# ospi_v143.net
KiCad netlist of a schematic drawn in EAGLE
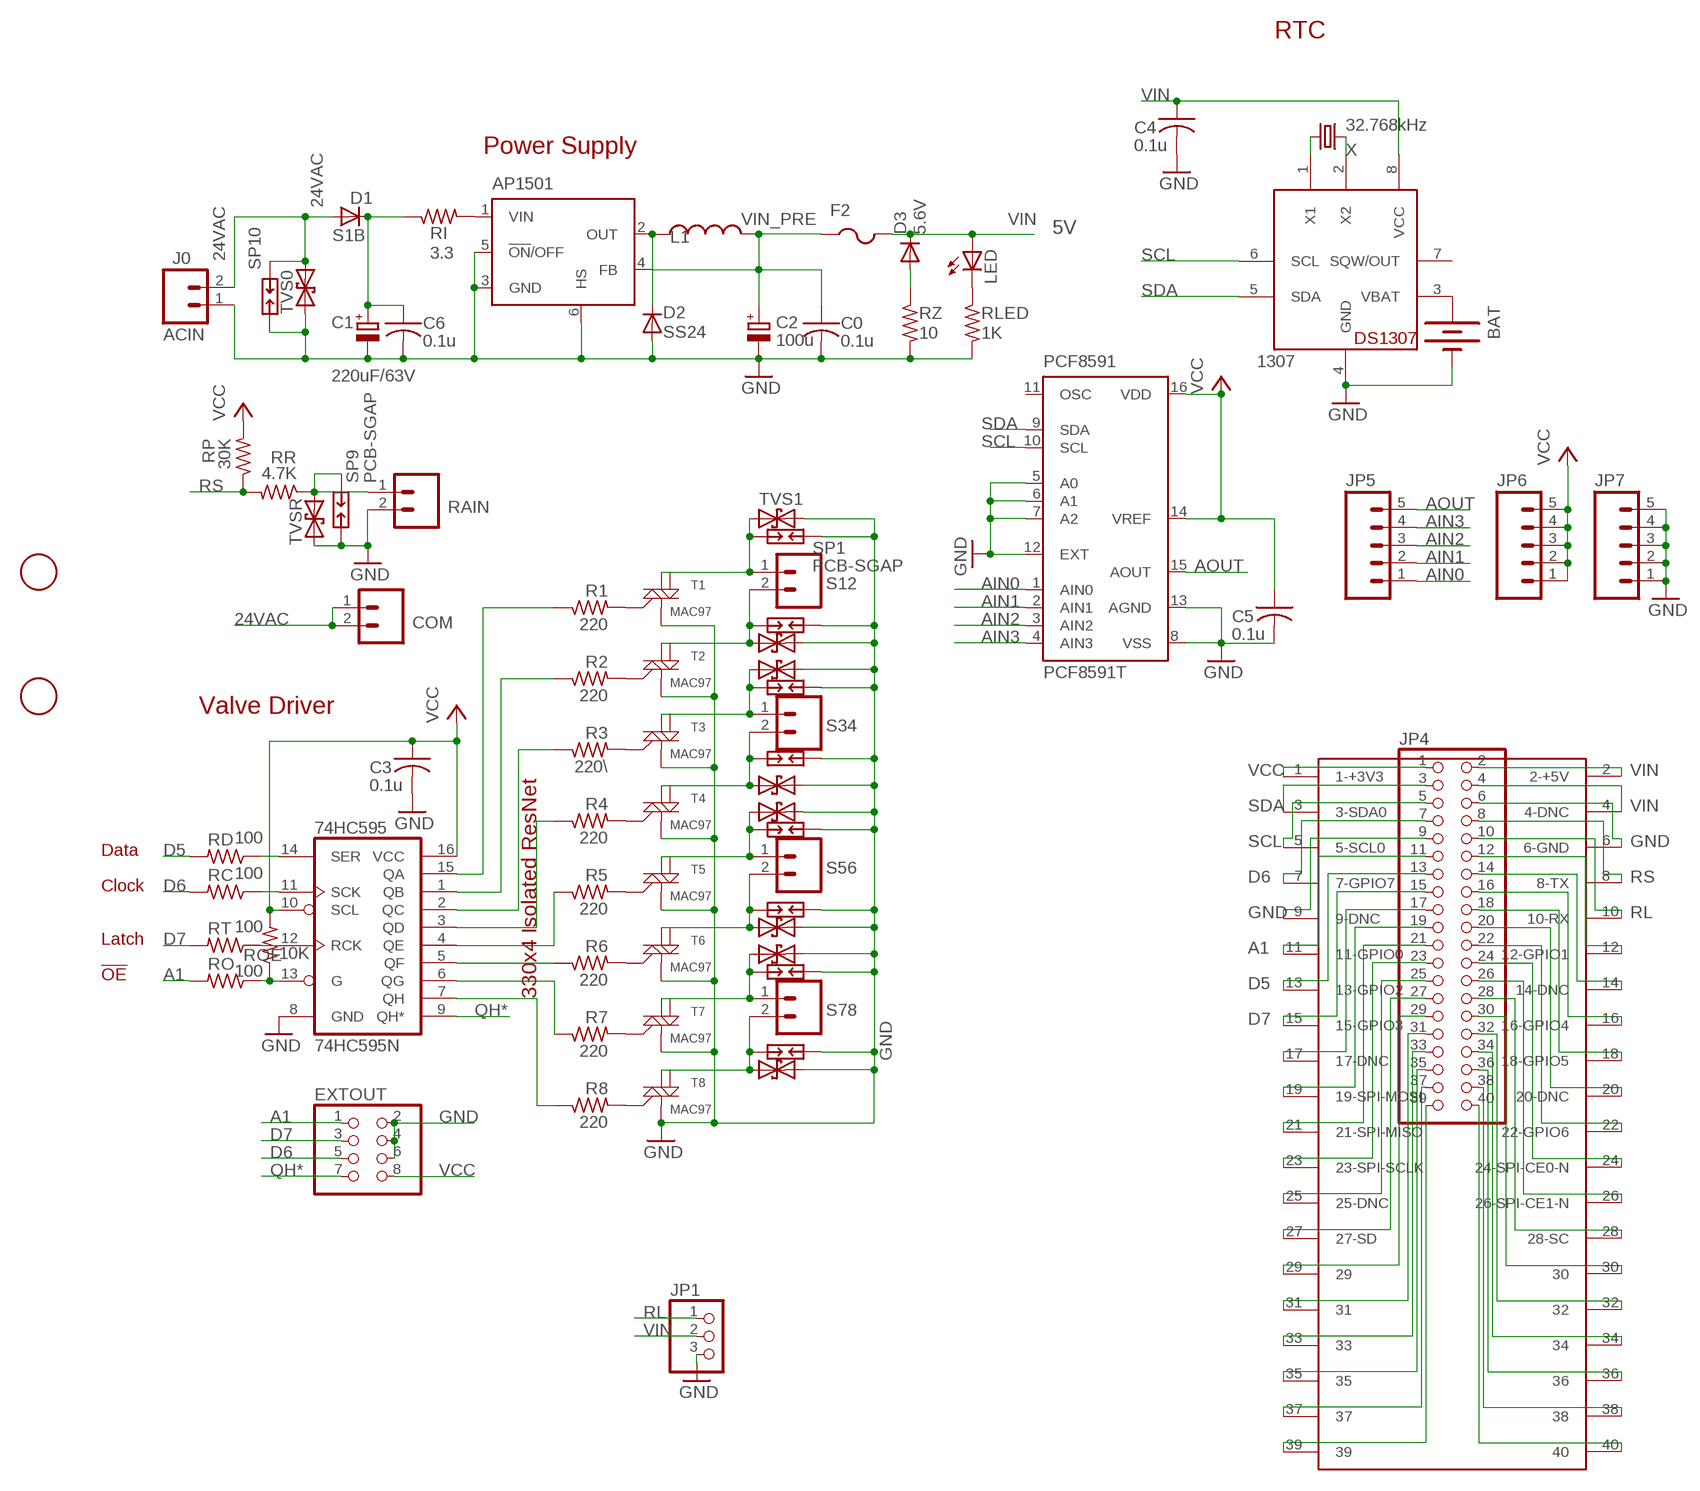
[diagram p0: schematic, sheet 1]

(export (version "E")
  (design (tool "Eeschema 10.0.6"))
  (components
    (comp (ref "74HC595")
      (value "74HC595N")
      (footprint "eagle-import:SO16")
      (libsource (lib "eagle-import") (part "74595DLS"))
    )
    (comp (ref "1307")
      (value "DS1307")
      (footprint "eagle-import:SO08")
      (libsource (lib "eagle-import") (part "DS1307SOIC"))
    )
    (comp (ref "AP1501")
      (value "LM2596S")
      (footprint "eagle-import:TO263-5")
      (fields (field (name "MF") "NATIONAL SEMICONDUCTOR") (field (name "MPN") "LM2596S-ADJ/NOPB"))
      (libsource (lib "eagle-import") (part "LM2596S"))
    )
    (comp (ref "BAT")
      (value "BATTERYBATTERY_12MM_SMT")
      (footprint "eagle-import:BATTCON_12MM_SMT")
      (libsource (lib "eagle-import") (part "BATTERYBATTERY_12MM_SMT"))
    )
    (comp (ref "C0")
      (value "0.1u")
      (footprint "eagle-import:C0603K")
      (libsource (lib "eagle-import") (part "C-USC0603K"))
    )
    (comp (ref "C1")
      (value "220uF/63V")
      (footprint "eagle-import:PANASONIC_E")
      (libsource (lib "eagle-import") (part "CPOL-EUE"))
    )
    (comp (ref "C2")
      (value "100u")
      (footprint "eagle-import:PANASONIC_E")
      (libsource (lib "eagle-import") (part "CPOL-EUE"))
    )
    (comp (ref "C3")
      (value "0.1u")
      (footprint "eagle-import:C0603K")
      (libsource (lib "eagle-import") (part "C-USC0603K"))
    )
    (comp (ref "C4")
      (value "0.1u")
      (footprint "eagle-import:C0603K")
      (libsource (lib "eagle-import") (part "C-USC0603K"))
    )
    (comp (ref "C5")
      (value "0.1u")
      (footprint "eagle-import:C0603K")
      (libsource (lib "eagle-import") (part "C-USC0603K"))
    )
    (comp (ref "C6")
      (value "0.1u")
      (footprint "eagle-import:C0603K")
      (libsource (lib "eagle-import") (part "C-USC0603K"))
    )
    (comp (ref "COM")
      (value "M025MM-X")
      (footprint "eagle-import:SCREWTERMINAL-5MM-2-X")
      (libsource (lib "eagle-import") (part "M025MM-X"))
    )
    (comp (ref "D1")
      (value "S1B")
      (footprint "eagle-import:DO-214AC")
      (libsource (lib "eagle-import") (part "DIODE-DO-214AC"))
    )
    (comp (ref "D2")
      (value "SS24")
      (footprint "eagle-import:SMB")
      (libsource (lib "eagle-import") (part "DIODE-SMB"))
    )
    (comp (ref "D3")
      (value "5.6V")
      (footprint "eagle-import:MINIMELF")
      (libsource (lib "eagle-import") (part "DIODE-MINIMELF"))
    )
    (comp (ref "EXTOUT")
      (value "PINHD-2X4/90")
      (footprint "eagle-import:2X04_90")
      (libsource (lib "eagle-import") (part "PINHD-2X4/90"))
    )
    (comp (ref "F2")
      (value "PTCFUSE-1812")
      (footprint "eagle-import:1812")
      (libsource (lib "eagle-import") (part "PTCFUSE-1812"))
    )
    (comp (ref "J0")
      (value "ACIN")
      (footprint "eagle-import:SCREWTERMINAL-4MM-2-X")
      (libsource (lib "eagle-import") (part "M024MM-X"))
    )
    (comp (ref "JP1")
      (value "PINHD-1X3")
      (footprint "eagle-import:1X03")
      (libsource (lib "eagle-import") (part "PINHD-1X3"))
    )
    (comp (ref "JP4")
      (value "PINHD-2X20")
      (footprint "eagle-import:2X20")
      (libsource (lib "eagle-import") (part "PINHD-2X20"))
    )
    (comp (ref "JP5")
      (value "M05PTH")
      (footprint "eagle-import:1X05")
      (libsource (lib "eagle-import") (part "M05PTH"))
    )
    (comp (ref "JP6")
      (value "M05PTH")
      (footprint "eagle-import:1X05")
      (libsource (lib "eagle-import") (part "M05PTH"))
    )
    (comp (ref "JP7")
      (value "M05PTH")
      (footprint "eagle-import:1X05")
      (libsource (lib "eagle-import") (part "M05PTH"))
    )
    (comp (ref "L1")
      (value "150uH")
      (footprint "eagle-import:CDRH125")
      (libsource (lib "eagle-import") (part "INDUCTORPWR"))
    )
    (comp (ref "LED")
      (value "LEDCHIPLED_0805")
      (footprint "eagle-import:CHIPLED_0805")
      (libsource (lib "eagle-import") (part "LEDCHIPLED_0805"))
    )
    (comp (ref "PCF8591")
      (value "PCF8591T")
      (footprint "eagle-import:SO16W")
      (fields (field (name "MPN") "PCF8591T/2,512"))
      (libsource (lib "eagle-import") (part "PCF8591T"))
    )
    (comp (ref "R1")
      (value "220")
      (footprint "eagle-import:R0603")
      (libsource (lib "eagle-import") (part "R-US_R0603"))
    )
    (comp (ref "R2")
      (value "220")
      (footprint "eagle-import:R0603")
      (libsource (lib "eagle-import") (part "R-US_R0603"))
    )
    (comp (ref "R3")
      (value "220\\")
      (footprint "eagle-import:R0603")
      (libsource (lib "eagle-import") (part "R-US_R0603"))
    )
    (comp (ref "R4")
      (value "220")
      (footprint "eagle-import:R0603")
      (libsource (lib "eagle-import") (part "R-US_R0603"))
    )
    (comp (ref "R5")
      (value "220")
      (footprint "eagle-import:R0603")
      (libsource (lib "eagle-import") (part "R-US_R0603"))
    )
    (comp (ref "R6")
      (value "220")
      (footprint "eagle-import:R0603")
      (libsource (lib "eagle-import") (part "R-US_R0603"))
    )
    (comp (ref "R7")
      (value "220")
      (footprint "eagle-import:R0603")
      (libsource (lib "eagle-import") (part "R-US_R0603"))
    )
    (comp (ref "R8")
      (value "220")
      (footprint "eagle-import:R0603")
      (libsource (lib "eagle-import") (part "R-US_R0603"))
    )
    (comp (ref "RAIN")
      (value "M025MM-X")
      (footprint "eagle-import:SCREWTERMINAL-5MM-2-X")
      (libsource (lib "eagle-import") (part "M025MM-X"))
    )
    (comp (ref "RC")
      (value "100")
      (footprint "eagle-import:R0603")
      (libsource (lib "eagle-import") (part "R-US_R0603"))
    )
    (comp (ref "RD")
      (value "100")
      (footprint "eagle-import:R0603")
      (libsource (lib "eagle-import") (part "R-US_R0603"))
    )
    (comp (ref "RI")
      (value "3.3")
      (footprint "eagle-import:R2010")
      (libsource (lib "eagle-import") (part "adafruitGood_R-US_R2010"))
    )
    (comp (ref "RLED")
      (value "1K")
      (footprint "eagle-import:R0805")
      (libsource (lib "eagle-import") (part "R-US_R0805"))
    )
    (comp (ref "RO")
      (value "100")
      (footprint "eagle-import:R0603")
      (libsource (lib "eagle-import") (part "R-US_R0603"))
    )
    (comp (ref "ROE")
      (value "10K")
      (footprint "eagle-import:R0603")
      (libsource (lib "eagle-import") (part "R-US_R0603"))
    )
    (comp (ref "RP")
      (value "30K")
      (footprint "eagle-import:R0805")
      (libsource (lib "eagle-import") (part "R-US_R0805"))
    )
    (comp (ref "RR")
      (value "4.7K")
      (footprint "eagle-import:R0805")
      (libsource (lib "eagle-import") (part "R-US_R0805"))
    )
    (comp (ref "RT")
      (value "100")
      (footprint "eagle-import:R0603")
      (libsource (lib "eagle-import") (part "R-US_R0603"))
    )
    (comp (ref "RZ")
      (value "10")
      (footprint "eagle-import:R2010")
      (libsource (lib "eagle-import") (part "R-US_R2010"))
    )
    (comp (ref "S12")
      (value "M025MM-X")
      (footprint "eagle-import:SCREWTERMINAL-5MM-2-X")
      (libsource (lib "eagle-import") (part "M025MM-X"))
    )
    (comp (ref "S34")
      (value "M025MM-X")
      (footprint "eagle-import:SCREWTERMINAL-5MM-2-X")
      (libsource (lib "eagle-import") (part "M025MM-X"))
    )
    (comp (ref "S56")
      (value "M025MM-X")
      (footprint "eagle-import:SCREWTERMINAL-5MM-2-X")
      (libsource (lib "eagle-import") (part "M025MM-X"))
    )
    (comp (ref "S78")
      (value "M025MM-X")
      (footprint "eagle-import:SCREWTERMINAL-5MM-2-X")
      (libsource (lib "eagle-import") (part "M025MM-X"))
    )
    (comp (ref "SP1")
      (value "PCB-SGAP")
      (footprint "eagle-import:PCB-SGAP")
      (libsource (lib "eagle-import") (part "PCB-SGAP"))
    )
    (comp (ref "SP2")
      (value "PCB-SGAP")
      (footprint "eagle-import:PCB-SGAP")
      (libsource (lib "eagle-import") (part "PCB-SGAP"))
    )
    (comp (ref "SP3")
      (value "PCB-SGAP")
      (footprint "eagle-import:PCB-SGAP")
      (libsource (lib "eagle-import") (part "PCB-SGAP"))
    )
    (comp (ref "SP4")
      (value "PCB-SGAP")
      (footprint "eagle-import:PCB-SGAP")
      (libsource (lib "eagle-import") (part "PCB-SGAP"))
    )
    (comp (ref "SP5")
      (value "PCB-SGAP")
      (footprint "eagle-import:PCB-SGAP")
      (libsource (lib "eagle-import") (part "PCB-SGAP"))
    )
    (comp (ref "SP6")
      (value "PCB-SGAP")
      (footprint "eagle-import:PCB-SGAP")
      (libsource (lib "eagle-import") (part "PCB-SGAP"))
    )
    (comp (ref "SP7")
      (value "PCB-SGAP")
      (footprint "eagle-import:PCB-SGAP")
      (libsource (lib "eagle-import") (part "PCB-SGAP"))
    )
    (comp (ref "SP8")
      (value "PCB-SGAP")
      (footprint "eagle-import:PCB-SGAP")
      (libsource (lib "eagle-import") (part "PCB-SGAP"))
    )
    (comp (ref "SP9")
      (value "PCB-SGAP")
      (footprint "eagle-import:PCB-SGAP")
      (libsource (lib "eagle-import") (part "PCB-SGAP"))
    )
    (comp (ref "SP10")
      (value "PCB-SGAP")
      (footprint "eagle-import:PCB-SGAP")
      (libsource (lib "eagle-import") (part "PCB-SGAP"))
    )
    (comp (ref "T1")
      (value "MAC97")
      (footprint "eagle-import:SOT223")
      (libsource (lib "eagle-import") (part "MAC97SOT223"))
    )
    (comp (ref "T2")
      (value "MAC97")
      (footprint "eagle-import:SOT223")
      (libsource (lib "eagle-import") (part "MAC97SOT223"))
    )
    (comp (ref "T3")
      (value "MAC97")
      (footprint "eagle-import:SOT223")
      (libsource (lib "eagle-import") (part "MAC97SOT223"))
    )
    (comp (ref "T4")
      (value "MAC97")
      (footprint "eagle-import:SOT223")
      (libsource (lib "eagle-import") (part "MAC97SOT223"))
    )
    (comp (ref "T5")
      (value "MAC97")
      (footprint "eagle-import:SOT223")
      (libsource (lib "eagle-import") (part "MAC97SOT223"))
    )
    (comp (ref "T6")
      (value "MAC97")
      (footprint "eagle-import:SOT223")
      (libsource (lib "eagle-import") (part "MAC97SOT223"))
    )
    (comp (ref "T7")
      (value "MAC97")
      (footprint "eagle-import:SOT223")
      (libsource (lib "eagle-import") (part "MAC97SOT223"))
    )
    (comp (ref "T8")
      (value "MAC97")
      (footprint "eagle-import:SOT223")
      (libsource (lib "eagle-import") (part "MAC97SOT223"))
    )
    (comp (ref "TVS0")
      (value "TVSSMB")
      (footprint "eagle-import:SMB")
      (libsource (lib "eagle-import") (part "TVSSMB"))
    )
    (comp (ref "TVS1")
      (value "TVSSMB")
      (footprint "eagle-import:SMB")
      (libsource (lib "eagle-import") (part "TVSSMB"))
    )
    (comp (ref "TVS2")
      (value "TVSSMB")
      (footprint "eagle-import:SMB")
      (libsource (lib "eagle-import") (part "TVSSMB"))
    )
    (comp (ref "TVS3")
      (value "TVSSMB")
      (footprint "eagle-import:SMB")
      (libsource (lib "eagle-import") (part "TVSSMB"))
    )
    (comp (ref "TVS4")
      (value "TVSSMB")
      (footprint "eagle-import:SMB")
      (libsource (lib "eagle-import") (part "TVSSMB"))
    )
    (comp (ref "TVS5")
      (value "TVSSMB")
      (footprint "eagle-import:SMB")
      (libsource (lib "eagle-import") (part "TVSSMB"))
    )
    (comp (ref "TVS6")
      (value "TVSSMB")
      (footprint "eagle-import:SMB")
      (libsource (lib "eagle-import") (part "TVSSMB"))
    )
    (comp (ref "TVS7")
      (value "TVSSMB")
      (footprint "eagle-import:SMB")
      (libsource (lib "eagle-import") (part "TVSSMB"))
    )
    (comp (ref "TVS8")
      (value "TVSSMB")
      (footprint "eagle-import:SMB")
      (libsource (lib "eagle-import") (part "TVSSMB"))
    )
    (comp (ref "TVSR")
      (value "TVSSMB")
      (footprint "eagle-import:SMB")
      (libsource (lib "eagle-import") (part "TVSSMB"))
    )
    (comp (ref "U$1")
      (value "FIDUCIAL")
      (footprint "eagle-import:FIDUCIAL_1MM")
      (libsource (lib "eagle-import") (part "FIDUCIAL"))
    )
    (comp (ref "U$2")
      (value "RPIB+")
      (footprint "eagle-import:RPIB+")
      (libsource (lib "eagle-import") (part "RPIB+"))
    )
    (comp (ref "U$3")
      (value "FIDUCIAL")
      (footprint "eagle-import:FIDUCIAL_1MM")
      (libsource (lib "eagle-import") (part "FIDUCIAL"))
    )
    (comp (ref "X")
      (value "32.768kHz")
      (footprint "eagle-import:MM20SS")
      (libsource (lib "eagle-import") (part "CRYSTALMM20SS"))
    )
  )
  (nets
    (net (code "1") (name "/24VAC") (class "Default")
      (node (ref "COM") (pin "1") (pinfunction "1_1") (pintype "passive"))
      (node (ref "COM") (pin "2") (pinfunction "2_2") (pintype "passive"))
      (node (ref "D1") (pin "A") (pinfunction "A_A") (pintype "passive"))
      (node (ref "J0") (pin "2") (pinfunction "2_2") (pintype "passive"))
      (node (ref "SP10") (pin "1") (pinfunction "1_1") (pintype "passive"))
      (node (ref "TVS0") (pin "C") (pinfunction "C_C") (pintype "passive"))
    )
    (net (code "2") (name "/A1") (class "Default")
      (node (ref "EXTOUT") (pin "1") (pinfunction "1_1") (pintype "passive"))
      (node (ref "JP4") (pin "11") (pinfunction "11_11") (pintype "passive"))
      (node (ref "RO") (pin "2") (pinfunction "2_2") (pintype "passive"))
      (node (ref "U$2") (pin "11") (pinfunction "11-GPIO0_11") (pintype "bidirectional"))
    )
    (net (code "3") (name "/AIN0") (class "Default")
      (node (ref "JP5") (pin "1") (pinfunction "1_1") (pintype "passive"))
      (node (ref "PCF8591") (pin "1") (pinfunction "AIN0_1") (pintype "input"))
    )
    (net (code "4") (name "/AIN1") (class "Default")
      (node (ref "JP5") (pin "2") (pinfunction "2_2") (pintype "passive"))
      (node (ref "PCF8591") (pin "2") (pinfunction "AIN1_2") (pintype "input"))
    )
    (net (code "5") (name "/AIN2") (class "Default")
      (node (ref "JP5") (pin "3") (pinfunction "3_3") (pintype "passive"))
      (node (ref "PCF8591") (pin "3") (pinfunction "AIN2_3") (pintype "input"))
    )
    (net (code "6") (name "/AIN3") (class "Default")
      (node (ref "JP5") (pin "4") (pinfunction "4_4") (pintype "passive"))
      (node (ref "PCF8591") (pin "4") (pinfunction "AIN3_4") (pintype "input"))
    )
    (net (code "7") (name "/AOUT") (class "Default")
      (node (ref "JP5") (pin "5") (pinfunction "5_5") (pintype "passive"))
      (node (ref "PCF8591") (pin "15") (pinfunction "AOUT_15") (pintype "output"))
    )
    (net (code "8") (name "/D5") (class "Default")
      (node (ref "JP4") (pin "13") (pinfunction "13_13") (pintype "passive"))
      (node (ref "RD") (pin "2") (pinfunction "2_2") (pintype "passive"))
      (node (ref "U$2") (pin "13") (pinfunction "13-GPIO2_13") (pintype "bidirectional"))
    )
    (net (code "9") (name "/D6") (class "Default")
      (node (ref "EXTOUT") (pin "5") (pinfunction "5_5") (pintype "passive"))
      (node (ref "JP4") (pin "7") (pinfunction "7_7") (pintype "passive"))
      (node (ref "RC") (pin "2") (pinfunction "2_2") (pintype "passive"))
      (node (ref "U$2") (pin "7") (pinfunction "7-GPIO7_7") (pintype "bidirectional"))
    )
    (net (code "10") (name "/D7") (class "Default")
      (node (ref "EXTOUT") (pin "3") (pinfunction "3_3") (pintype "passive"))
      (node (ref "JP4") (pin "15") (pinfunction "15_15") (pintype "passive"))
      (node (ref "RT") (pin "2") (pinfunction "2_2") (pintype "passive"))
      (node (ref "U$2") (pin "15") (pinfunction "15-GPIO3_15") (pintype "bidirectional"))
    )
    (net (code "11") (name "/QH*") (class "Default")
      (node (ref "74HC595") (pin "9") (pinfunction "QH*_9") (pintype "tri_state"))
      (node (ref "EXTOUT") (pin "7") (pinfunction "7_7") (pintype "passive"))
    )
    (net (code "12") (name "/RL") (class "Default")
      (node (ref "JP1") (pin "1") (pinfunction "1_1") (pintype "passive"))
      (node (ref "JP4") (pin "10") (pinfunction "10_10") (pintype "passive"))
      (node (ref "U$2") (pin "10") (pinfunction "10-RX_10") (pintype "bidirectional"))
    )
    (net (code "13") (name "/RS") (class "Default")
      (node (ref "JP4") (pin "8") (pinfunction "8_8") (pintype "passive"))
      (node (ref "RP") (pin "1") (pinfunction "1_1") (pintype "passive"))
      (node (ref "RR") (pin "2") (pinfunction "2_2") (pintype "passive"))
      (node (ref "U$2") (pin "8") (pinfunction "8-TX_8") (pintype "bidirectional"))
    )
    (net (code "14") (name "/SCL") (class "Default")
      (node (ref "1307") (pin "6") (pinfunction "SCL_6") (pintype "bidirectional"))
      (node (ref "JP4") (pin "5") (pinfunction "5_5") (pintype "passive"))
      (node (ref "PCF8591") (pin "10") (pinfunction "SCL_10") (pintype "input"))
      (node (ref "U$2") (pin "5") (pinfunction "5-SCL0_5") (pintype "bidirectional"))
    )
    (net (code "15") (name "/SDA") (class "Default")
      (node (ref "1307") (pin "5") (pinfunction "SDA_5") (pintype "bidirectional"))
      (node (ref "JP4") (pin "3") (pinfunction "3_3") (pintype "passive"))
      (node (ref "PCF8591") (pin "9") (pinfunction "SDA_9") (pintype "bidirectional"))
      (node (ref "U$2") (pin "3") (pinfunction "3-SDA0_3") (pintype "bidirectional"))
    )
    (net (code "16") (name "/VIN") (class "Default")
      (node (ref "1307") (pin "8") (pinfunction "VCC_8") (pintype "power_in"))
      (node (ref "C4") (pin "1") (pinfunction "1_1") (pintype "passive"))
      (node (ref "D3") (pin "C") (pinfunction "C_C") (pintype "passive"))
      (node (ref "F2") (pin "2") (pinfunction "2_2") (pintype "passive"))
      (node (ref "JP1") (pin "2") (pinfunction "2_2") (pintype "passive"))
      (node (ref "JP4") (pin "2") (pinfunction "2_2") (pintype "passive"))
      (node (ref "JP4") (pin "4") (pinfunction "4_4") (pintype "passive"))
      (node (ref "LED") (pin "A") (pinfunction "A_A") (pintype "passive"))
      (node (ref "U$2") (pin "2") (pinfunction "2-+5V_2") (pintype "bidirectional"))
      (node (ref "U$2") (pin "4") (pinfunction "4-DNC_4") (pintype "bidirectional"))
    )
    (net (code "17") (name "/VIN_PRE") (class "Default")
      (node (ref "AP1501") (pin "4") (pinfunction "FB_4") (pintype "input"))
      (node (ref "C0") (pin "1") (pinfunction "1_1") (pintype "passive"))
      (node (ref "C2") (pin "+") (pinfunction "+_+") (pintype "passive"))
      (node (ref "F2") (pin "1") (pinfunction "1_1") (pintype "passive"))
      (node (ref "L1") (pin "2") (pinfunction "2_2") (pintype "passive"))
    )
    (net (code "18") (name "GND") (class "Default")
      (node (ref "1307") (pin "4") (pinfunction "GND_4") (pintype "power_in"))
      (node (ref "74HC595") (pin "8") (pinfunction "GND_8") (pintype "power_in"))
      (node (ref "AP1501") (pin "3") (pinfunction "GND_3") (pintype "power_in"))
      (node (ref "AP1501") (pin "5") (pinfunction "~{ON}/OFF_5") (pintype "input"))
      (node (ref "AP1501") (pin "6") (pinfunction "HS_6") (pintype "power_in"))
      (node (ref "BAT") (pin "P$1") (pinfunction "-_P$1") (pintype "power_in"))
      (node (ref "C0") (pin "2") (pinfunction "2_2") (pintype "passive"))
      (node (ref "C1") (pin "-") (pinfunction "-_-") (pintype "passive"))
      (node (ref "C2") (pin "-") (pinfunction "-_-") (pintype "passive"))
      (node (ref "C3") (pin "2") (pinfunction "2_2") (pintype "passive"))
      (node (ref "C4") (pin "2") (pinfunction "2_2") (pintype "passive"))
      (node (ref "C5") (pin "2") (pinfunction "2_2") (pintype "passive"))
      (node (ref "C6") (pin "2") (pinfunction "2_2") (pintype "passive"))
      (node (ref "D2") (pin "A") (pinfunction "A_A") (pintype "passive"))
      (node (ref "EXTOUT") (pin "2") (pinfunction "2_2") (pintype "passive"))
      (node (ref "EXTOUT") (pin "4") (pinfunction "4_4") (pintype "passive"))
      (node (ref "EXTOUT") (pin "6") (pinfunction "6_6") (pintype "passive"))
      (node (ref "J0") (pin "1") (pinfunction "1_1") (pintype "passive"))
      (node (ref "JP1") (pin "3") (pinfunction "3_3") (pintype "passive"))
      (node (ref "JP4") (pin "6") (pinfunction "6_6") (pintype "passive"))
      (node (ref "JP4") (pin "9") (pinfunction "9_9") (pintype "passive"))
      (node (ref "JP7") (pin "1") (pinfunction "1_1") (pintype "passive"))
      (node (ref "JP7") (pin "2") (pinfunction "2_2") (pintype "passive"))
      (node (ref "JP7") (pin "3") (pinfunction "3_3") (pintype "passive"))
      (node (ref "JP7") (pin "4") (pinfunction "4_4") (pintype "passive"))
      (node (ref "JP7") (pin "5") (pinfunction "5_5") (pintype "passive"))
      (node (ref "PCF8591") (pin "12") (pinfunction "EXT_12") (pintype "input"))
      (node (ref "PCF8591") (pin "13") (pinfunction "AGND_13") (pintype "power_in"))
      (node (ref "PCF8591") (pin "5") (pinfunction "A0_5") (pintype "input"))
      (node (ref "PCF8591") (pin "6") (pinfunction "A1_6") (pintype "input"))
      (node (ref "PCF8591") (pin "7") (pinfunction "A2_7") (pintype "input"))
      (node (ref "PCF8591") (pin "8") (pinfunction "VSS_8") (pintype "power_in"))
      (node (ref "RAIN") (pin "2") (pinfunction "2_2") (pintype "passive"))
      (node (ref "RLED") (pin "2") (pinfunction "2_2") (pintype "passive"))
      (node (ref "RZ") (pin "2") (pinfunction "2_2") (pintype "passive"))
      (node (ref "SP1") (pin "1") (pinfunction "1_1") (pintype "passive"))
      (node (ref "SP10") (pin "2") (pinfunction "2_2") (pintype "passive"))
      (node (ref "SP2") (pin "1") (pinfunction "1_1") (pintype "passive"))
      (node (ref "SP3") (pin "1") (pinfunction "1_1") (pintype "passive"))
      (node (ref "SP4") (pin "1") (pinfunction "1_1") (pintype "passive"))
      (node (ref "SP5") (pin "1") (pinfunction "1_1") (pintype "passive"))
      (node (ref "SP6") (pin "1") (pinfunction "1_1") (pintype "passive"))
      (node (ref "SP7") (pin "1") (pinfunction "1_1") (pintype "passive"))
      (node (ref "SP8") (pin "1") (pinfunction "1_1") (pintype "passive"))
      (node (ref "SP9") (pin "2") (pinfunction "2_2") (pintype "passive"))
      (node (ref "T1") (pin "1") (pinfunction "M1_1") (pintype "bidirectional"))
      (node (ref "T2") (pin "1") (pinfunction "M1_1") (pintype "bidirectional"))
      (node (ref "T3") (pin "1") (pinfunction "M1_1") (pintype "bidirectional"))
      (node (ref "T4") (pin "1") (pinfunction "M1_1") (pintype "bidirectional"))
      (node (ref "T5") (pin "1") (pinfunction "M1_1") (pintype "bidirectional"))
      (node (ref "T6") (pin "1") (pinfunction "M1_1") (pintype "bidirectional"))
      (node (ref "T7") (pin "1") (pinfunction "M1_1") (pintype "bidirectional"))
      (node (ref "T8") (pin "1") (pinfunction "M1_1") (pintype "bidirectional"))
      (node (ref "TVS0") (pin "A") (pinfunction "A_A") (pintype "passive"))
      (node (ref "TVS1") (pin "C") (pinfunction "C_C") (pintype "passive"))
      (node (ref "TVS2") (pin "C") (pinfunction "C_C") (pintype "passive"))
      (node (ref "TVS3") (pin "C") (pinfunction "C_C") (pintype "passive"))
      (node (ref "TVS4") (pin "C") (pinfunction "C_C") (pintype "passive"))
      (node (ref "TVS5") (pin "C") (pinfunction "C_C") (pintype "passive"))
      (node (ref "TVS6") (pin "C") (pinfunction "C_C") (pintype "passive"))
      (node (ref "TVS7") (pin "C") (pinfunction "C_C") (pintype "passive"))
      (node (ref "TVS8") (pin "C") (pinfunction "C_C") (pintype "passive"))
      (node (ref "TVSR") (pin "A") (pinfunction "A_A") (pintype "passive"))
      (node (ref "U$2") (pin "6") (pinfunction "6-GND_6") (pintype "bidirectional"))
      (node (ref "U$2") (pin "9") (pinfunction "9-DNC_9") (pintype "bidirectional"))
    )
    (net (code "19") (name "Net-(74HC595-G)") (class "Default")
      (node (ref "74HC595") (pin "13") (pinfunction "G_13") (pintype "input"))
      (node (ref "RO") (pin "1") (pinfunction "1_1") (pintype "passive"))
      (node (ref "ROE") (pin "1") (pinfunction "1_1") (pintype "passive"))
    )
    (net (code "20") (name "Net-(74HC595-QA)") (class "Default")
      (node (ref "74HC595") (pin "15") (pinfunction "QA_15") (pintype "tri_state"))
      (node (ref "R1") (pin "1") (pinfunction "1_1") (pintype "passive"))
    )
    (net (code "21") (name "Net-(74HC595-QB)") (class "Default")
      (node (ref "74HC595") (pin "1") (pinfunction "QB_1") (pintype "tri_state"))
      (node (ref "R2") (pin "1") (pinfunction "1_1") (pintype "passive"))
    )
    (net (code "22") (name "Net-(74HC595-QC)") (class "Default")
      (node (ref "74HC595") (pin "2") (pinfunction "QC_2") (pintype "tri_state"))
      (node (ref "R3") (pin "1") (pinfunction "1_1") (pintype "passive"))
    )
    (net (code "23") (name "Net-(74HC595-QD)") (class "Default")
      (node (ref "74HC595") (pin "3") (pinfunction "QD_3") (pintype "tri_state"))
      (node (ref "R4") (pin "1") (pinfunction "1_1") (pintype "passive"))
    )
    (net (code "24") (name "Net-(74HC595-QE)") (class "Default")
      (node (ref "74HC595") (pin "4") (pinfunction "QE_4") (pintype "tri_state"))
      (node (ref "R5") (pin "1") (pinfunction "1_1") (pintype "passive"))
    )
    (net (code "25") (name "Net-(74HC595-QF)") (class "Default")
      (node (ref "74HC595") (pin "5") (pinfunction "QF_5") (pintype "tri_state"))
      (node (ref "R6") (pin "1") (pinfunction "1_1") (pintype "passive"))
    )
    (net (code "26") (name "Net-(74HC595-QG)") (class "Default")
      (node (ref "74HC595") (pin "6") (pinfunction "QG_6") (pintype "tri_state"))
      (node (ref "R7") (pin "1") (pinfunction "1_1") (pintype "passive"))
    )
    (net (code "27") (name "Net-(74HC595-QH)") (class "Default")
      (node (ref "74HC595") (pin "7") (pinfunction "QH_7") (pintype "tri_state"))
      (node (ref "R8") (pin "1") (pinfunction "1_1") (pintype "passive"))
    )
    (net (code "28") (name "Net-(74HC595-RCK)") (class "Default")
      (node (ref "74HC595") (pin "12") (pinfunction "RCK_12") (pintype "input"))
      (node (ref "RT") (pin "1") (pinfunction "1_1") (pintype "passive"))
    )
    (net (code "29") (name "Net-(74HC595-SCK)") (class "Default")
      (node (ref "74HC595") (pin "11") (pinfunction "SCK_11") (pintype "input"))
      (node (ref "RC") (pin "1") (pinfunction "1_1") (pintype "passive"))
    )
    (net (code "30") (name "Net-(74HC595-SER)") (class "Default")
      (node (ref "74HC595") (pin "14") (pinfunction "SER_14") (pintype "input"))
      (node (ref "RD") (pin "1") (pinfunction "1_1") (pintype "passive"))
    )
    (net (code "31") (name "Net-(1307-VBAT)") (class "Default")
      (node (ref "1307") (pin "3") (pinfunction "VBAT_3") (pintype "power_in"))
      (node (ref "BAT") (pin "P$2") (pinfunction "+_P$2") (pintype "power_in"))
    )
    (net (code "32") (name "Net-(1307-X1)") (class "Default")
      (node (ref "1307") (pin "1") (pinfunction "X1_1") (pintype "passive"))
      (node (ref "X") (pin "1") (pinfunction "1_1") (pintype "passive"))
    )
    (net (code "33") (name "Net-(1307-X2)") (class "Default")
      (node (ref "1307") (pin "2") (pinfunction "X2_2") (pintype "passive"))
      (node (ref "X") (pin "4") (pinfunction "2_4") (pintype "passive"))
    )
    (net (code "34") (name "Net-(AP1501-OUT)") (class "Default")
      (node (ref "AP1501") (pin "2") (pinfunction "OUT_2") (pintype "output"))
      (node (ref "D2") (pin "C") (pinfunction "C_C") (pintype "passive"))
      (node (ref "L1") (pin "1") (pinfunction "1_1") (pintype "passive"))
    )
    (net (code "35") (name "Net-(AP1501-VIN)") (class "Default")
      (node (ref "AP1501") (pin "1") (pinfunction "VIN_1") (pintype "input"))
      (node (ref "RI") (pin "2") (pinfunction "2_2") (pintype "passive"))
    )
    (net (code "36") (name "Net-(C1-Pad+)") (class "Default")
      (node (ref "C1") (pin "+") (pinfunction "+_+") (pintype "passive"))
      (node (ref "C6") (pin "1") (pinfunction "1_1") (pintype "passive"))
      (node (ref "D1") (pin "C") (pinfunction "C_C") (pintype "passive"))
      (node (ref "RI") (pin "1") (pinfunction "1_1") (pintype "passive"))
    )
    (net (code "37") (name "Net-(D3-PadA)") (class "Default")
      (node (ref "D3") (pin "A") (pinfunction "A_A") (pintype "passive"))
      (node (ref "RZ") (pin "1") (pinfunction "1_1") (pintype "passive"))
    )
    (net (code "38") (name "Net-(JP4-Pad29)") (class "Default")
      (node (ref "JP4") (pin "29") (pinfunction "29_29") (pintype "passive"))
      (node (ref "U$2") (pin "29") (pinfunction "29_29") (pintype "bidirectional"))
    )
    (net (code "39") (name "Net-(JP4-Pad30)") (class "Default")
      (node (ref "JP4") (pin "30") (pinfunction "30_30") (pintype "passive"))
      (node (ref "U$2") (pin "30") (pinfunction "30_30") (pintype "bidirectional"))
    )
    (net (code "40") (name "Net-(JP4-Pad31)") (class "Default")
      (node (ref "JP4") (pin "31") (pinfunction "31_31") (pintype "passive"))
      (node (ref "U$2") (pin "31") (pinfunction "31_31") (pintype "bidirectional"))
    )
    (net (code "41") (name "Net-(JP4-Pad32)") (class "Default")
      (node (ref "JP4") (pin "32") (pinfunction "32_32") (pintype "passive"))
      (node (ref "U$2") (pin "32") (pinfunction "32_32") (pintype "bidirectional"))
    )
    (net (code "42") (name "Net-(JP4-Pad33)") (class "Default")
      (node (ref "JP4") (pin "33") (pinfunction "33_33") (pintype "passive"))
      (node (ref "U$2") (pin "33") (pinfunction "33_33") (pintype "bidirectional"))
    )
    (net (code "43") (name "Net-(JP4-Pad34)") (class "Default")
      (node (ref "JP4") (pin "34") (pinfunction "34_34") (pintype "passive"))
      (node (ref "U$2") (pin "34") (pinfunction "34_34") (pintype "bidirectional"))
    )
    (net (code "44") (name "Net-(JP4-Pad35)") (class "Default")
      (node (ref "JP4") (pin "35") (pinfunction "35_35") (pintype "passive"))
      (node (ref "U$2") (pin "35") (pinfunction "35_35") (pintype "bidirectional"))
    )
    (net (code "45") (name "Net-(JP4-Pad36)") (class "Default")
      (node (ref "JP4") (pin "36") (pinfunction "36_36") (pintype "passive"))
      (node (ref "U$2") (pin "36") (pinfunction "36_36") (pintype "bidirectional"))
    )
    (net (code "46") (name "Net-(JP4-Pad37)") (class "Default")
      (node (ref "JP4") (pin "37") (pinfunction "37_37") (pintype "passive"))
      (node (ref "U$2") (pin "37") (pinfunction "37_37") (pintype "bidirectional"))
    )
    (net (code "47") (name "Net-(JP4-Pad38)") (class "Default")
      (node (ref "JP4") (pin "38") (pinfunction "38_38") (pintype "passive"))
      (node (ref "U$2") (pin "38") (pinfunction "38_38") (pintype "bidirectional"))
    )
    (net (code "48") (name "Net-(JP4-Pad39)") (class "Default")
      (node (ref "JP4") (pin "39") (pinfunction "39_39") (pintype "passive"))
      (node (ref "U$2") (pin "39") (pinfunction "39_39") (pintype "bidirectional"))
    )
    (net (code "49") (name "Net-(JP4-Pad40)") (class "Default")
      (node (ref "JP4") (pin "40") (pinfunction "40_40") (pintype "passive"))
      (node (ref "U$2") (pin "40") (pinfunction "40_40") (pintype "bidirectional"))
    )
    (net (code "50") (name "Net-(LED-PadC)") (class "Default")
      (node (ref "LED") (pin "C") (pinfunction "C_C") (pintype "passive"))
      (node (ref "RLED") (pin "1") (pinfunction "1_1") (pintype "passive"))
    )
    (net (code "51") (name "Net-(RAIN-Pad1)") (class "Default")
      (node (ref "RAIN") (pin "1") (pinfunction "1_1") (pintype "passive"))
      (node (ref "RR") (pin "1") (pinfunction "1_1") (pintype "passive"))
      (node (ref "SP9") (pin "1") (pinfunction "1_1") (pintype "passive"))
      (node (ref "TVSR") (pin "C") (pinfunction "C_C") (pintype "passive"))
    )
    (net (code "52") (name "Net-(T1-G)") (class "Default")
      (node (ref "R1") (pin "2") (pinfunction "2_2") (pintype "passive"))
      (node (ref "T1") (pin "3") (pinfunction "G_3") (pintype "bidirectional"))
    )
    (net (code "53") (name "Net-(T1-M2)") (class "Default")
      (node (ref "S12") (pin "1") (pinfunction "1_1") (pintype "passive"))
      (node (ref "SP1") (pin "2") (pinfunction "2_2") (pintype "passive"))
      (node (ref "T1") (pin "2") (pinfunction "M2_2") (pintype "bidirectional"))
      (node (ref "TVS1") (pin "A") (pinfunction "A_A") (pintype "passive"))
    )
    (net (code "54") (name "Net-(T2-G)") (class "Default")
      (node (ref "R2") (pin "2") (pinfunction "2_2") (pintype "passive"))
      (node (ref "T2") (pin "3") (pinfunction "G_3") (pintype "bidirectional"))
    )
    (net (code "55") (name "Net-(T2-M2)") (class "Default")
      (node (ref "S12") (pin "2") (pinfunction "2_2") (pintype "passive"))
      (node (ref "SP2") (pin "2") (pinfunction "2_2") (pintype "passive"))
      (node (ref "T2") (pin "2") (pinfunction "M2_2") (pintype "bidirectional"))
      (node (ref "TVS2") (pin "A") (pinfunction "A_A") (pintype "passive"))
    )
    (net (code "56") (name "Net-(T3-G)") (class "Default")
      (node (ref "R3") (pin "2") (pinfunction "2_2") (pintype "passive"))
      (node (ref "T3") (pin "3") (pinfunction "G_3") (pintype "bidirectional"))
    )
    (net (code "57") (name "Net-(T3-M2)") (class "Default")
      (node (ref "S34") (pin "1") (pinfunction "1_1") (pintype "passive"))
      (node (ref "SP3") (pin "2") (pinfunction "2_2") (pintype "passive"))
      (node (ref "T3") (pin "2") (pinfunction "M2_2") (pintype "bidirectional"))
      (node (ref "TVS3") (pin "A") (pinfunction "A_A") (pintype "passive"))
    )
    (net (code "58") (name "Net-(T4-G)") (class "Default")
      (node (ref "R4") (pin "2") (pinfunction "2_2") (pintype "passive"))
      (node (ref "T4") (pin "3") (pinfunction "G_3") (pintype "bidirectional"))
    )
    (net (code "59") (name "Net-(T4-M2)") (class "Default")
      (node (ref "S34") (pin "2") (pinfunction "2_2") (pintype "passive"))
      (node (ref "SP4") (pin "2") (pinfunction "2_2") (pintype "passive"))
      (node (ref "T4") (pin "2") (pinfunction "M2_2") (pintype "bidirectional"))
      (node (ref "TVS4") (pin "A") (pinfunction "A_A") (pintype "passive"))
    )
    (net (code "60") (name "Net-(T5-G)") (class "Default")
      (node (ref "R5") (pin "2") (pinfunction "2_2") (pintype "passive"))
      (node (ref "T5") (pin "3") (pinfunction "G_3") (pintype "bidirectional"))
    )
    (net (code "61") (name "Net-(T5-M2)") (class "Default")
      (node (ref "S56") (pin "1") (pinfunction "1_1") (pintype "passive"))
      (node (ref "SP5") (pin "2") (pinfunction "2_2") (pintype "passive"))
      (node (ref "T5") (pin "2") (pinfunction "M2_2") (pintype "bidirectional"))
      (node (ref "TVS5") (pin "A") (pinfunction "A_A") (pintype "passive"))
    )
    (net (code "62") (name "Net-(T6-G)") (class "Default")
      (node (ref "R6") (pin "2") (pinfunction "2_2") (pintype "passive"))
      (node (ref "T6") (pin "3") (pinfunction "G_3") (pintype "bidirectional"))
    )
    (net (code "63") (name "Net-(T6-M2)") (class "Default")
      (node (ref "S56") (pin "2") (pinfunction "2_2") (pintype "passive"))
      (node (ref "SP6") (pin "2") (pinfunction "2_2") (pintype "passive"))
      (node (ref "T6") (pin "2") (pinfunction "M2_2") (pintype "bidirectional"))
      (node (ref "TVS6") (pin "A") (pinfunction "A_A") (pintype "passive"))
    )
    (net (code "64") (name "Net-(T7-G)") (class "Default")
      (node (ref "R7") (pin "2") (pinfunction "2_2") (pintype "passive"))
      (node (ref "T7") (pin "3") (pinfunction "G_3") (pintype "bidirectional"))
    )
    (net (code "65") (name "Net-(T7-M2)") (class "Default")
      (node (ref "S78") (pin "1") (pinfunction "1_1") (pintype "passive"))
      (node (ref "SP7") (pin "2") (pinfunction "2_2") (pintype "passive"))
      (node (ref "T7") (pin "2") (pinfunction "M2_2") (pintype "bidirectional"))
      (node (ref "TVS7") (pin "A") (pinfunction "A_A") (pintype "passive"))
    )
    (net (code "66") (name "Net-(T8-G)") (class "Default")
      (node (ref "R8") (pin "2") (pinfunction "2_2") (pintype "passive"))
      (node (ref "T8") (pin "3") (pinfunction "G_3") (pintype "bidirectional"))
    )
    (net (code "67") (name "Net-(T8-M2)") (class "Default")
      (node (ref "S78") (pin "2") (pinfunction "2_2") (pintype "passive"))
      (node (ref "SP8") (pin "2") (pinfunction "2_2") (pintype "passive"))
      (node (ref "T8") (pin "2") (pinfunction "M2_2") (pintype "bidirectional"))
      (node (ref "TVS8") (pin "A") (pinfunction "A_A") (pintype "passive"))
    )
    (net (code "68") (name "Net-(U$2-12-GPIO1)") (class "Default")
      (node (ref "JP4") (pin "12") (pinfunction "12_12") (pintype "passive"))
      (node (ref "U$2") (pin "12") (pinfunction "12-GPIO1_12") (pintype "bidirectional"))
    )
    (net (code "69") (name "Net-(U$2-14-DNC)") (class "Default")
      (node (ref "JP4") (pin "14") (pinfunction "14_14") (pintype "passive"))
      (node (ref "U$2") (pin "14") (pinfunction "14-DNC_14") (pintype "bidirectional"))
    )
    (net (code "70") (name "Net-(U$2-16-GPIO4)") (class "Default")
      (node (ref "JP4") (pin "16") (pinfunction "16_16") (pintype "passive"))
      (node (ref "U$2") (pin "16") (pinfunction "16-GPIO4_16") (pintype "bidirectional"))
    )
    (net (code "71") (name "Net-(U$2-17-DNC)") (class "Default")
      (node (ref "JP4") (pin "17") (pinfunction "17_17") (pintype "passive"))
      (node (ref "U$2") (pin "17") (pinfunction "17-DNC_17") (pintype "bidirectional"))
    )
    (net (code "72") (name "Net-(U$2-18-GPIO5)") (class "Default")
      (node (ref "JP4") (pin "18") (pinfunction "18_18") (pintype "passive"))
      (node (ref "U$2") (pin "18") (pinfunction "18-GPIO5_18") (pintype "bidirectional"))
    )
    (net (code "73") (name "Net-(U$2-19-SPI-MOSI)") (class "Default")
      (node (ref "JP4") (pin "19") (pinfunction "19_19") (pintype "passive"))
      (node (ref "U$2") (pin "19") (pinfunction "19-SPI-MOSI_19") (pintype "bidirectional"))
    )
    (net (code "74") (name "Net-(U$2-20-DNC)") (class "Default")
      (node (ref "JP4") (pin "20") (pinfunction "20_20") (pintype "passive"))
      (node (ref "U$2") (pin "20") (pinfunction "20-DNC_20") (pintype "bidirectional"))
    )
    (net (code "75") (name "Net-(U$2-21-SPI-MISO)") (class "Default")
      (node (ref "JP4") (pin "21") (pinfunction "21_21") (pintype "passive"))
      (node (ref "U$2") (pin "21") (pinfunction "21-SPI-MISO_21") (pintype "bidirectional"))
    )
    (net (code "76") (name "Net-(U$2-22-GPIO6)") (class "Default")
      (node (ref "JP4") (pin "22") (pinfunction "22_22") (pintype "passive"))
      (node (ref "U$2") (pin "22") (pinfunction "22-GPIO6_22") (pintype "bidirectional"))
    )
    (net (code "77") (name "Net-(U$2-23-SPI-SCLK)") (class "Default")
      (node (ref "JP4") (pin "23") (pinfunction "23_23") (pintype "passive"))
      (node (ref "U$2") (pin "23") (pinfunction "23-SPI-SCLK_23") (pintype "bidirectional"))
    )
    (net (code "78") (name "Net-(U$2-24-SPI-CE0-N)") (class "Default")
      (node (ref "JP4") (pin "24") (pinfunction "24_24") (pintype "passive"))
      (node (ref "U$2") (pin "24") (pinfunction "24-SPI-CE0-N_24") (pintype "bidirectional"))
    )
    (net (code "79") (name "Net-(U$2-25-DNC)") (class "Default")
      (node (ref "JP4") (pin "25") (pinfunction "25_25") (pintype "passive"))
      (node (ref "U$2") (pin "25") (pinfunction "25-DNC_25") (pintype "bidirectional"))
    )
    (net (code "80") (name "Net-(U$2-26-SPI-CE1-N)") (class "Default")
      (node (ref "JP4") (pin "26") (pinfunction "26_26") (pintype "passive"))
      (node (ref "U$2") (pin "26") (pinfunction "26-SPI-CE1-N_26") (pintype "bidirectional"))
    )
    (net (code "81") (name "Net-(U$2-27-SD)") (class "Default")
      (node (ref "JP4") (pin "27") (pinfunction "27_27") (pintype "passive"))
      (node (ref "U$2") (pin "27") (pinfunction "27-SD_27") (pintype "bidirectional"))
    )
    (net (code "82") (name "Net-(U$2-28-SC)") (class "Default")
      (node (ref "JP4") (pin "28") (pinfunction "28_28") (pintype "passive"))
      (node (ref "U$2") (pin "28") (pinfunction "28-SC_28") (pintype "bidirectional"))
    )
    (net (code "83") (name "VCC") (class "Default")
      (node (ref "74HC595") (pin "10") (pinfunction "SCL_10") (pintype "input"))
      (node (ref "74HC595") (pin "16") (pinfunction "VCC_16") (pintype "power_in"))
      (node (ref "C3") (pin "1") (pinfunction "1_1") (pintype "passive"))
      (node (ref "C5") (pin "1") (pinfunction "1_1") (pintype "passive"))
      (node (ref "EXTOUT") (pin "8") (pinfunction "8_8") (pintype "passive"))
      (node (ref "JP4") (pin "1") (pinfunction "1_1") (pintype "passive"))
      (node (ref "JP6") (pin "1") (pinfunction "1_1") (pintype "passive"))
      (node (ref "JP6") (pin "2") (pinfunction "2_2") (pintype "passive"))
      (node (ref "JP6") (pin "3") (pinfunction "3_3") (pintype "passive"))
      (node (ref "JP6") (pin "4") (pinfunction "4_4") (pintype "passive"))
      (node (ref "JP6") (pin "5") (pinfunction "5_5") (pintype "passive"))
      (node (ref "PCF8591") (pin "14") (pinfunction "VREF_14") (pintype "input"))
      (node (ref "PCF8591") (pin "16") (pinfunction "VDD_16") (pintype "power_in"))
      (node (ref "ROE") (pin "2") (pinfunction "2_2") (pintype "passive"))
      (node (ref "RP") (pin "2") (pinfunction "2_2") (pintype "passive"))
      (node (ref "U$2") (pin "1") (pinfunction "1-+3V3_1") (pintype "bidirectional"))
    )
    (net (code "84") (name "unconnected-(1307-SQW{slash}OUT-Pad7)") (class "Default")
      (node (ref "1307") (pin "7") (pinfunction "SQW/OUT_7") (pintype "bidirectional"))
    )
    (net (code "85") (name "unconnected-(PCF8591-OSC-Pad11)") (class "Default")
      (node (ref "PCF8591") (pin "11") (pinfunction "OSC_11") (pintype "input"))
    )
    (net (code "86") (name "unconnected-(T1-M2-4-Pad4)") (class "Default")
      (node (ref "T1") (pin "4") (pinfunction "M2-4_4") (pintype "bidirectional"))
    )
    (net (code "87") (name "unconnected-(T2-M2-4-Pad4)") (class "Default")
      (node (ref "T2") (pin "4") (pinfunction "M2-4_4") (pintype "bidirectional"))
    )
    (net (code "88") (name "unconnected-(T3-M2-4-Pad4)") (class "Default")
      (node (ref "T3") (pin "4") (pinfunction "M2-4_4") (pintype "bidirectional"))
    )
    (net (code "89") (name "unconnected-(T4-M2-4-Pad4)") (class "Default")
      (node (ref "T4") (pin "4") (pinfunction "M2-4_4") (pintype "bidirectional"))
    )
    (net (code "90") (name "unconnected-(T5-M2-4-Pad4)") (class "Default")
      (node (ref "T5") (pin "4") (pinfunction "M2-4_4") (pintype "bidirectional"))
    )
    (net (code "91") (name "unconnected-(T6-M2-4-Pad4)") (class "Default")
      (node (ref "T6") (pin "4") (pinfunction "M2-4_4") (pintype "bidirectional"))
    )
    (net (code "92") (name "unconnected-(T7-M2-4-Pad4)") (class "Default")
      (node (ref "T7") (pin "4") (pinfunction "M2-4_4") (pintype "bidirectional"))
    )
    (net (code "93") (name "unconnected-(T8-M2-4-Pad4)") (class "Default")
      (node (ref "T8") (pin "4") (pinfunction "M2-4_4") (pintype "bidirectional"))
    )
  )
)
